# ram.net
KiCad netlist of a schematic drawn in Altium Designer
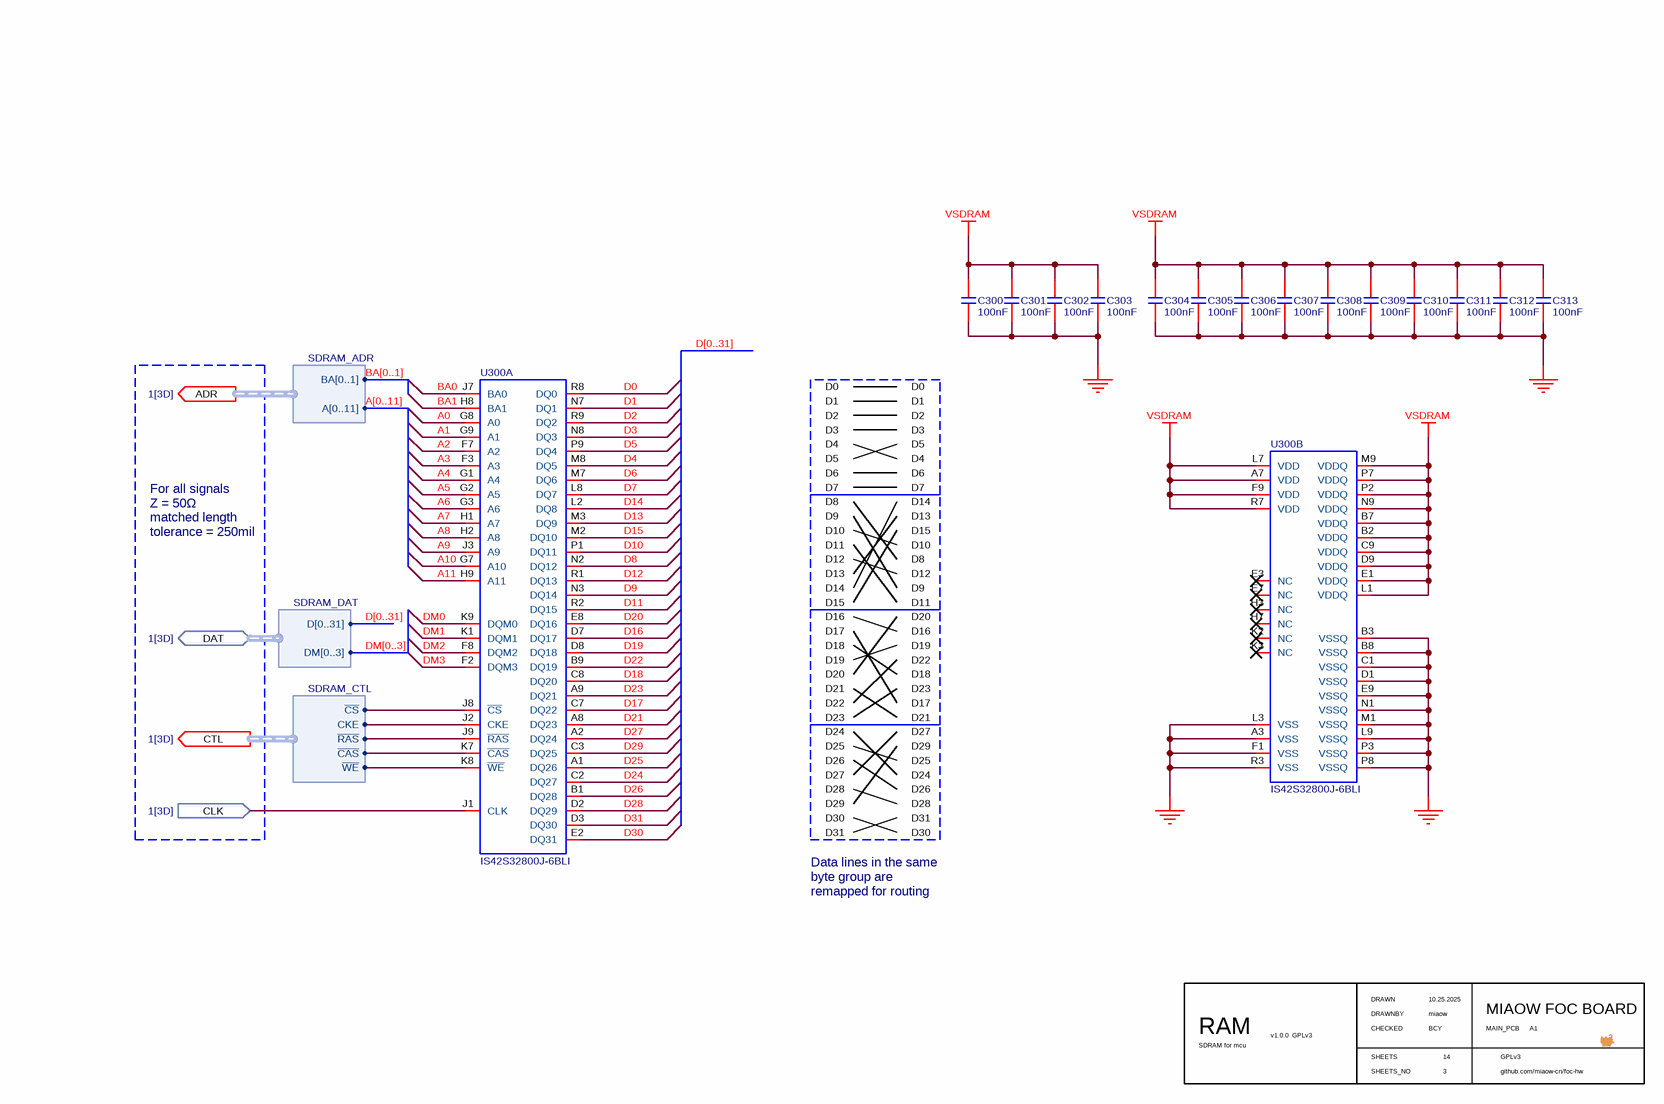
[diagram p0: ram.schdoc]

(export (version "E")
  (design (tool "Eeschema 10.0.6"))
  (components
    (comp (ref "C300")
      (value "100nF")
      (footprint "mw:C0402")
      (fields (field (name "VOLTAGE") "25V") (field (name "Comment") "C-NOMO"))
      (libsource (lib "mw") (part "C-NOMO"))
    )
    (comp (ref "C301")
      (value "100nF")
      (footprint "mw:C0402")
      (fields (field (name "VOLTAGE") "25V") (field (name "Comment") "C-NOMO"))
      (libsource (lib "mw") (part "C-NOMO"))
    )
    (comp (ref "C302")
      (value "100nF")
      (footprint "mw:C0402")
      (fields (field (name "VOLTAGE") "25V") (field (name "Comment") "C-NOMO"))
      (libsource (lib "mw") (part "C-NOMO"))
    )
    (comp (ref "C303")
      (value "100nF")
      (footprint "mw:C0402")
      (fields (field (name "VOLTAGE") "25V") (field (name "Comment") "C-NOMO"))
      (libsource (lib "mw") (part "C-NOMO"))
    )
    (comp (ref "C304")
      (value "100nF")
      (footprint "mw:C0402")
      (fields (field (name "VOLTAGE") "25V") (field (name "Comment") "C-NOMO"))
      (libsource (lib "mw") (part "C-NOMO"))
    )
    (comp (ref "C305")
      (value "100nF")
      (footprint "mw:C0402")
      (fields (field (name "VOLTAGE") "25V") (field (name "Comment") "C-NOMO"))
      (libsource (lib "mw") (part "C-NOMO"))
    )
    (comp (ref "C306")
      (value "100nF")
      (footprint "mw:C0402")
      (fields (field (name "VOLTAGE") "25V") (field (name "Comment") "C-NOMO"))
      (libsource (lib "mw") (part "C-NOMO"))
    )
    (comp (ref "C307")
      (value "100nF")
      (footprint "mw:C0402")
      (fields (field (name "VOLTAGE") "25V") (field (name "Comment") "C-NOMO"))
      (libsource (lib "mw") (part "C-NOMO"))
    )
    (comp (ref "C308")
      (value "100nF")
      (footprint "mw:C0402")
      (fields (field (name "VOLTAGE") "25V") (field (name "Comment") "C-NOMO"))
      (libsource (lib "mw") (part "C-NOMO"))
    )
    (comp (ref "C309")
      (value "100nF")
      (footprint "mw:C0402")
      (fields (field (name "VOLTAGE") "25V") (field (name "Comment") "C-NOMO"))
      (libsource (lib "mw") (part "C-NOMO"))
    )
    (comp (ref "C310")
      (value "100nF")
      (footprint "mw:C0402")
      (fields (field (name "VOLTAGE") "25V") (field (name "Comment") "C-NOMO"))
      (libsource (lib "mw") (part "C-NOMO"))
    )
    (comp (ref "C311")
      (value "100nF")
      (footprint "mw:C0402")
      (fields (field (name "VOLTAGE") "25V") (field (name "Comment") "C-NOMO"))
      (libsource (lib "mw") (part "C-NOMO"))
    )
    (comp (ref "C312")
      (value "100nF")
      (footprint "mw:C0402")
      (fields (field (name "VOLTAGE") "25V") (field (name "Comment") "C-NOMO"))
      (libsource (lib "mw") (part "C-NOMO"))
    )
    (comp (ref "C313")
      (value "100nF")
      (footprint "mw:C0402")
      (fields (field (name "VOLTAGE") "25V") (field (name "Comment") "C-NOMO"))
      (libsource (lib "mw") (part "C-NOMO"))
    )
    (comp (ref "U300")
      (value "IS42S32800J-6BLI")
      (footprint "mw:IS42S32800J-6BLI")
      (libsource (lib "mw") (part "IS42S32800J-6BLI"))
    )
  )
  (nets
    (net (code "3") (name "/A0") (class "Default")
      (node (ref "U300") (pin "G8") (pinfunction "A0_G8") (pintype "passive"))
    )
    (net (code "4") (name "/A1") (class "Default")
      (node (ref "U300") (pin "G9") (pinfunction "A1_G9") (pintype "passive"))
    )
    (net (code "5") (name "/A2") (class "Default")
      (node (ref "U300") (pin "F7") (pinfunction "A2_F7") (pintype "passive"))
    )
    (net (code "6") (name "/A3") (class "Default")
      (node (ref "U300") (pin "F3") (pinfunction "A3_F3") (pintype "passive"))
    )
    (net (code "7") (name "/A4") (class "Default")
      (node (ref "U300") (pin "G1") (pinfunction "A4_G1") (pintype "passive"))
    )
    (net (code "8") (name "/A5") (class "Default")
      (node (ref "U300") (pin "G2") (pinfunction "A5_G2") (pintype "passive"))
    )
    (net (code "9") (name "/A6") (class "Default")
      (node (ref "U300") (pin "G3") (pinfunction "A6_G3") (pintype "passive"))
    )
    (net (code "10") (name "/A7") (class "Default")
      (node (ref "U300") (pin "H1") (pinfunction "A7_H1") (pintype "passive"))
    )
    (net (code "11") (name "/A8") (class "Default")
      (node (ref "U300") (pin "H2") (pinfunction "A8_H2") (pintype "passive"))
    )
    (net (code "12") (name "/A9") (class "Default")
      (node (ref "U300") (pin "J3") (pinfunction "A9_J3") (pintype "passive"))
    )
    (net (code "13") (name "/A10") (class "Default")
      (node (ref "U300") (pin "G7") (pinfunction "A10_G7") (pintype "passive"))
    )
    (net (code "14") (name "/A11") (class "Default")
      (node (ref "U300") (pin "H9") (pinfunction "A11_H9") (pintype "passive"))
    )
    (net (code "16") (name "/BA0") (class "Default")
      (node (ref "U300") (pin "J7") (pinfunction "BA0_J7") (pintype "passive"))
    )
    (net (code "17") (name "/BA1") (class "Default")
      (node (ref "U300") (pin "H8") (pinfunction "BA1_H8") (pintype "passive"))
    )
    (net (code "18") (name "/CKE") (class "Default")
      (node (ref "U300") (pin "J2") (pinfunction "CKE_J2") (pintype "passive"))
    )
    (net (code "19") (name "/CLK") (class "Default")
      (node (ref "U300") (pin "J1") (pinfunction "CLK_J1") (pintype "passive"))
    )
    (net (code "20") (name "/D0") (class "Default")
      (node (ref "U300") (pin "R8") (pinfunction "DQ0_R8") (pintype "passive"))
    )
    (net (code "21") (name "/D1") (class "Default")
      (node (ref "U300") (pin "N7") (pinfunction "DQ1_N7") (pintype "passive"))
    )
    (net (code "22") (name "/D2") (class "Default")
      (node (ref "U300") (pin "R9") (pinfunction "DQ2_R9") (pintype "passive"))
    )
    (net (code "23") (name "/D3") (class "Default")
      (node (ref "U300") (pin "N8") (pinfunction "DQ3_N8") (pintype "passive"))
    )
    (net (code "24") (name "/D4") (class "Default")
      (node (ref "U300") (pin "M8") (pinfunction "DQ5_M8") (pintype "passive"))
    )
    (net (code "25") (name "/D5") (class "Default")
      (node (ref "U300") (pin "P9") (pinfunction "DQ4_P9") (pintype "passive"))
    )
    (net (code "26") (name "/D6") (class "Default")
      (node (ref "U300") (pin "M7") (pinfunction "DQ6_M7") (pintype "passive"))
    )
    (net (code "27") (name "/D7") (class "Default")
      (node (ref "U300") (pin "L8") (pinfunction "DQ7_L8") (pintype "passive"))
    )
    (net (code "28") (name "/D8") (class "Default")
      (node (ref "U300") (pin "N2") (pinfunction "DQ12_N2") (pintype "passive"))
    )
    (net (code "29") (name "/D9") (class "Default")
      (node (ref "U300") (pin "N3") (pinfunction "DQ14_N3") (pintype "passive"))
    )
    (net (code "30") (name "/D10") (class "Default")
      (node (ref "U300") (pin "P1") (pinfunction "DQ11_P1") (pintype "passive"))
    )
    (net (code "31") (name "/D11") (class "Default")
      (node (ref "U300") (pin "R2") (pinfunction "DQ15_R2") (pintype "passive"))
    )
    (net (code "32") (name "/D12") (class "Default")
      (node (ref "U300") (pin "R1") (pinfunction "DQ13_R1") (pintype "passive"))
    )
    (net (code "33") (name "/D13") (class "Default")
      (node (ref "U300") (pin "M3") (pinfunction "DQ9_M3") (pintype "passive"))
    )
    (net (code "34") (name "/D14") (class "Default")
      (node (ref "U300") (pin "L2") (pinfunction "DQ8_L2") (pintype "passive"))
    )
    (net (code "35") (name "/D15") (class "Default")
      (node (ref "U300") (pin "M2") (pinfunction "DQ10_M2") (pintype "passive"))
    )
    (net (code "36") (name "/D16") (class "Default")
      (node (ref "U300") (pin "D7") (pinfunction "DQ17_D7") (pintype "passive"))
    )
    (net (code "37") (name "/D17") (class "Default")
      (node (ref "U300") (pin "C7") (pinfunction "DQ22_C7") (pintype "passive"))
    )
    (net (code "38") (name "/D18") (class "Default")
      (node (ref "U300") (pin "C8") (pinfunction "DQ20_C8") (pintype "passive"))
    )
    (net (code "39") (name "/D19") (class "Default")
      (node (ref "U300") (pin "D8") (pinfunction "DQ18_D8") (pintype "passive"))
    )
    (net (code "40") (name "/D20") (class "Default")
      (node (ref "U300") (pin "E8") (pinfunction "DQ16_E8") (pintype "passive"))
    )
    (net (code "41") (name "/D21") (class "Default")
      (node (ref "U300") (pin "A8") (pinfunction "DQ23_A8") (pintype "passive"))
    )
    (net (code "42") (name "/D22") (class "Default")
      (node (ref "U300") (pin "B9") (pinfunction "DQ19_B9") (pintype "passive"))
    )
    (net (code "43") (name "/D23") (class "Default")
      (node (ref "U300") (pin "A9") (pinfunction "DQ21_A9") (pintype "passive"))
    )
    (net (code "44") (name "/D24") (class "Default")
      (node (ref "U300") (pin "C2") (pinfunction "DQ27_C2") (pintype "passive"))
    )
    (net (code "45") (name "/D25") (class "Default")
      (node (ref "U300") (pin "A1") (pinfunction "DQ26_A1") (pintype "passive"))
    )
    (net (code "46") (name "/D26") (class "Default")
      (node (ref "U300") (pin "B1") (pinfunction "DQ28_B1") (pintype "passive"))
    )
    (net (code "47") (name "/D27") (class "Default")
      (node (ref "U300") (pin "A2") (pinfunction "DQ24_A2") (pintype "passive"))
    )
    (net (code "48") (name "/D28") (class "Default")
      (node (ref "U300") (pin "D2") (pinfunction "DQ29_D2") (pintype "passive"))
    )
    (net (code "49") (name "/D29") (class "Default")
      (node (ref "U300") (pin "C3") (pinfunction "DQ25_C3") (pintype "passive"))
    )
    (net (code "50") (name "/D30") (class "Default")
      (node (ref "U300") (pin "E2") (pinfunction "DQ31_E2") (pintype "passive"))
    )
    (net (code "51") (name "/D31") (class "Default")
      (node (ref "U300") (pin "D3") (pinfunction "DQ30_D3") (pintype "passive"))
    )
    (net (code "52") (name "/DM0") (class "Default")
      (node (ref "U300") (pin "K9") (pinfunction "DQM0_K9") (pintype "passive"))
    )
    (net (code "53") (name "/DM1") (class "Default")
      (node (ref "U300") (pin "K1") (pinfunction "DQM1_K1") (pintype "passive"))
    )
    (net (code "54") (name "/DM2") (class "Default")
      (node (ref "U300") (pin "F8") (pinfunction "DQM2_F8") (pintype "passive"))
    )
    (net (code "55") (name "/DM3") (class "Default")
      (node (ref "U300") (pin "F2") (pinfunction "DQM3_F2") (pintype "passive"))
    )
    (net (code "61") (name "/~{CAS}") (class "Default")
      (node (ref "U300") (pin "K7") (pinfunction "~{CAS}_K7") (pintype "passive"))
    )
    (net (code "62") (name "/~{CS}") (class "Default")
      (node (ref "U300") (pin "J8") (pinfunction "~{CS}_J8") (pintype "passive"))
    )
    (net (code "63") (name "/~{RAS}") (class "Default")
      (node (ref "U300") (pin "J9") (pinfunction "~{RAS}_J9") (pintype "passive"))
    )
    (net (code "64") (name "/~{WE}") (class "Default")
      (node (ref "U300") (pin "K8") (pinfunction "~{WE}_K8") (pintype "passive"))
    )
    (net (code "65") (name "GND") (class "Default")
      (node (ref "C300") (pin "1") (pinfunction "1_1") (pintype "passive"))
      (node (ref "C301") (pin "1") (pinfunction "1_1") (pintype "passive"))
      (node (ref "C302") (pin "1") (pinfunction "1_1") (pintype "passive"))
      (node (ref "C303") (pin "1") (pinfunction "1_1") (pintype "passive"))
      (node (ref "C304") (pin "1") (pinfunction "1_1") (pintype "passive"))
      (node (ref "C305") (pin "1") (pinfunction "1_1") (pintype "passive"))
      (node (ref "C306") (pin "1") (pinfunction "1_1") (pintype "passive"))
      (node (ref "C307") (pin "1") (pinfunction "1_1") (pintype "passive"))
      (node (ref "C308") (pin "1") (pinfunction "1_1") (pintype "passive"))
      (node (ref "C309") (pin "1") (pinfunction "1_1") (pintype "passive"))
      (node (ref "C310") (pin "1") (pinfunction "1_1") (pintype "passive"))
      (node (ref "C311") (pin "1") (pinfunction "1_1") (pintype "passive"))
      (node (ref "C312") (pin "1") (pinfunction "1_1") (pintype "passive"))
      (node (ref "C313") (pin "1") (pinfunction "1_1") (pintype "passive"))
      (node (ref "U300") (pin "A3") (pinfunction "VSS_A3") (pintype "passive"))
      (node (ref "U300") (pin "B3") (pinfunction "VSSQ_B3") (pintype "passive"))
      (node (ref "U300") (pin "B8") (pinfunction "VSSQ_B8") (pintype "passive"))
      (node (ref "U300") (pin "C1") (pinfunction "VSSQ_C1") (pintype "passive"))
      (node (ref "U300") (pin "D1") (pinfunction "VSSQ_D1") (pintype "passive"))
      (node (ref "U300") (pin "E9") (pinfunction "VSSQ_E9") (pintype "passive"))
      (node (ref "U300") (pin "F1") (pinfunction "VSS_F1") (pintype "passive"))
      (node (ref "U300") (pin "L3") (pinfunction "VSS_L3") (pintype "passive"))
      (node (ref "U300") (pin "L9") (pinfunction "VSSQ_L9") (pintype "passive"))
      (node (ref "U300") (pin "M1") (pinfunction "VSSQ_M1") (pintype "passive"))
      (node (ref "U300") (pin "N1") (pinfunction "VSSQ_N1") (pintype "passive"))
      (node (ref "U300") (pin "P3") (pinfunction "VSSQ_P3") (pintype "passive"))
      (node (ref "U300") (pin "P8") (pinfunction "VSSQ_P8") (pintype "passive"))
      (node (ref "U300") (pin "R3") (pinfunction "VSS_R3") (pintype "passive"))
    )
    (net (code "66") (name "VSDRAM") (class "Default")
      (node (ref "C300") (pin "2") (pinfunction "2_2") (pintype "passive"))
      (node (ref "C301") (pin "2") (pinfunction "2_2") (pintype "passive"))
      (node (ref "C302") (pin "2") (pinfunction "2_2") (pintype "passive"))
      (node (ref "C303") (pin "2") (pinfunction "2_2") (pintype "passive"))
      (node (ref "C304") (pin "2") (pinfunction "2_2") (pintype "passive"))
      (node (ref "C305") (pin "2") (pinfunction "2_2") (pintype "passive"))
      (node (ref "C306") (pin "2") (pinfunction "2_2") (pintype "passive"))
      (node (ref "C307") (pin "2") (pinfunction "2_2") (pintype "passive"))
      (node (ref "C308") (pin "2") (pinfunction "2_2") (pintype "passive"))
      (node (ref "C309") (pin "2") (pinfunction "2_2") (pintype "passive"))
      (node (ref "C310") (pin "2") (pinfunction "2_2") (pintype "passive"))
      (node (ref "C311") (pin "2") (pinfunction "2_2") (pintype "passive"))
      (node (ref "C312") (pin "2") (pinfunction "2_2") (pintype "passive"))
      (node (ref "C313") (pin "2") (pinfunction "2_2") (pintype "passive"))
      (node (ref "U300") (pin "A7") (pinfunction "VDD_A7") (pintype "passive"))
      (node (ref "U300") (pin "B2") (pinfunction "VDDQ_B2") (pintype "passive"))
      (node (ref "U300") (pin "B7") (pinfunction "VDDQ_B7") (pintype "passive"))
      (node (ref "U300") (pin "C9") (pinfunction "VDDQ_C9") (pintype "passive"))
      (node (ref "U300") (pin "D9") (pinfunction "VDDQ_D9") (pintype "passive"))
      (node (ref "U300") (pin "E1") (pinfunction "VDDQ_E1") (pintype "passive"))
      (node (ref "U300") (pin "F9") (pinfunction "VDD_F9") (pintype "passive"))
      (node (ref "U300") (pin "L1") (pinfunction "VDDQ_L1") (pintype "passive"))
      (node (ref "U300") (pin "L7") (pinfunction "VDD_L7") (pintype "passive"))
      (node (ref "U300") (pin "M9") (pinfunction "VDDQ_M9") (pintype "passive"))
      (node (ref "U300") (pin "N9") (pinfunction "VDDQ_N9") (pintype "passive"))
      (node (ref "U300") (pin "P2") (pinfunction "VDDQ_P2") (pintype "passive"))
      (node (ref "U300") (pin "P7") (pinfunction "VDDQ_P7") (pintype "passive"))
      (node (ref "U300") (pin "R7") (pinfunction "VDD_R7") (pintype "passive"))
    )
    (net (code "67") (name "unconnected-(U300B-NC-PadE3)") (class "Default")
      (node (ref "U300") (pin "E3") (pinfunction "NC_E3") (pintype "passive+no_connect"))
    )
    (net (code "68") (name "unconnected-(U300B-NC-PadE7)") (class "Default")
      (node (ref "U300") (pin "E7") (pinfunction "NC_E7") (pintype "passive+no_connect"))
    )
    (net (code "69") (name "unconnected-(U300B-NC-PadH3)") (class "Default")
      (node (ref "U300") (pin "H3") (pinfunction "NC_H3") (pintype "passive+no_connect"))
    )
    (net (code "70") (name "unconnected-(U300B-NC-PadH7)") (class "Default")
      (node (ref "U300") (pin "H7") (pinfunction "NC_H7") (pintype "passive+no_connect"))
    )
    (net (code "71") (name "unconnected-(U300B-NC-PadK2)") (class "Default")
      (node (ref "U300") (pin "K2") (pinfunction "NC_K2") (pintype "passive+no_connect"))
    )
    (net (code "72") (name "unconnected-(U300B-NC-PadK3)") (class "Default")
      (node (ref "U300") (pin "K3") (pinfunction "NC_K3") (pintype "passive+no_connect"))
    )
  )
)
